# untitled2.net
KiCad netlist of a schematic drawn in EAGLE
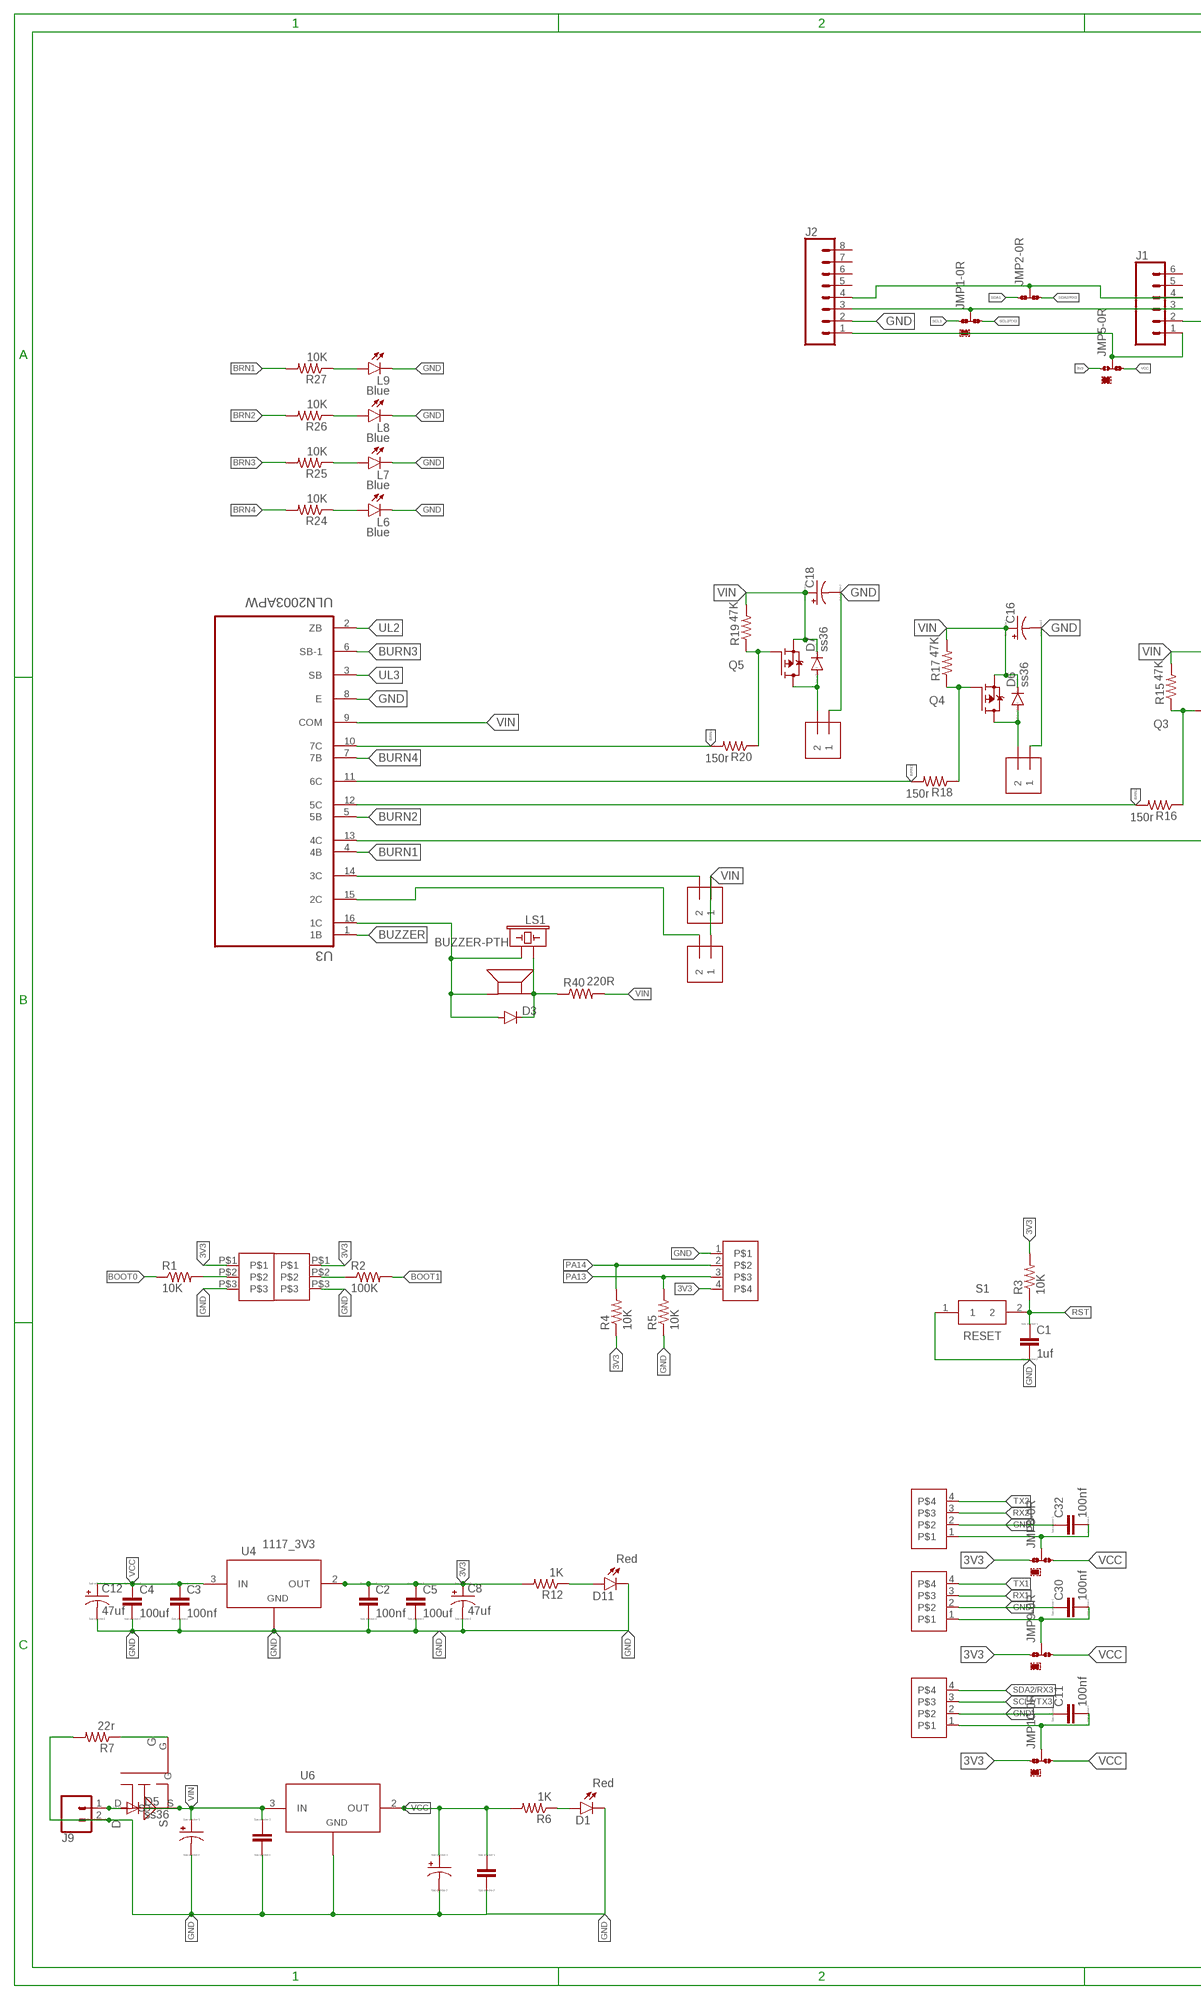
[diagram p0: schematic, sheet 1, part 1 of 2]
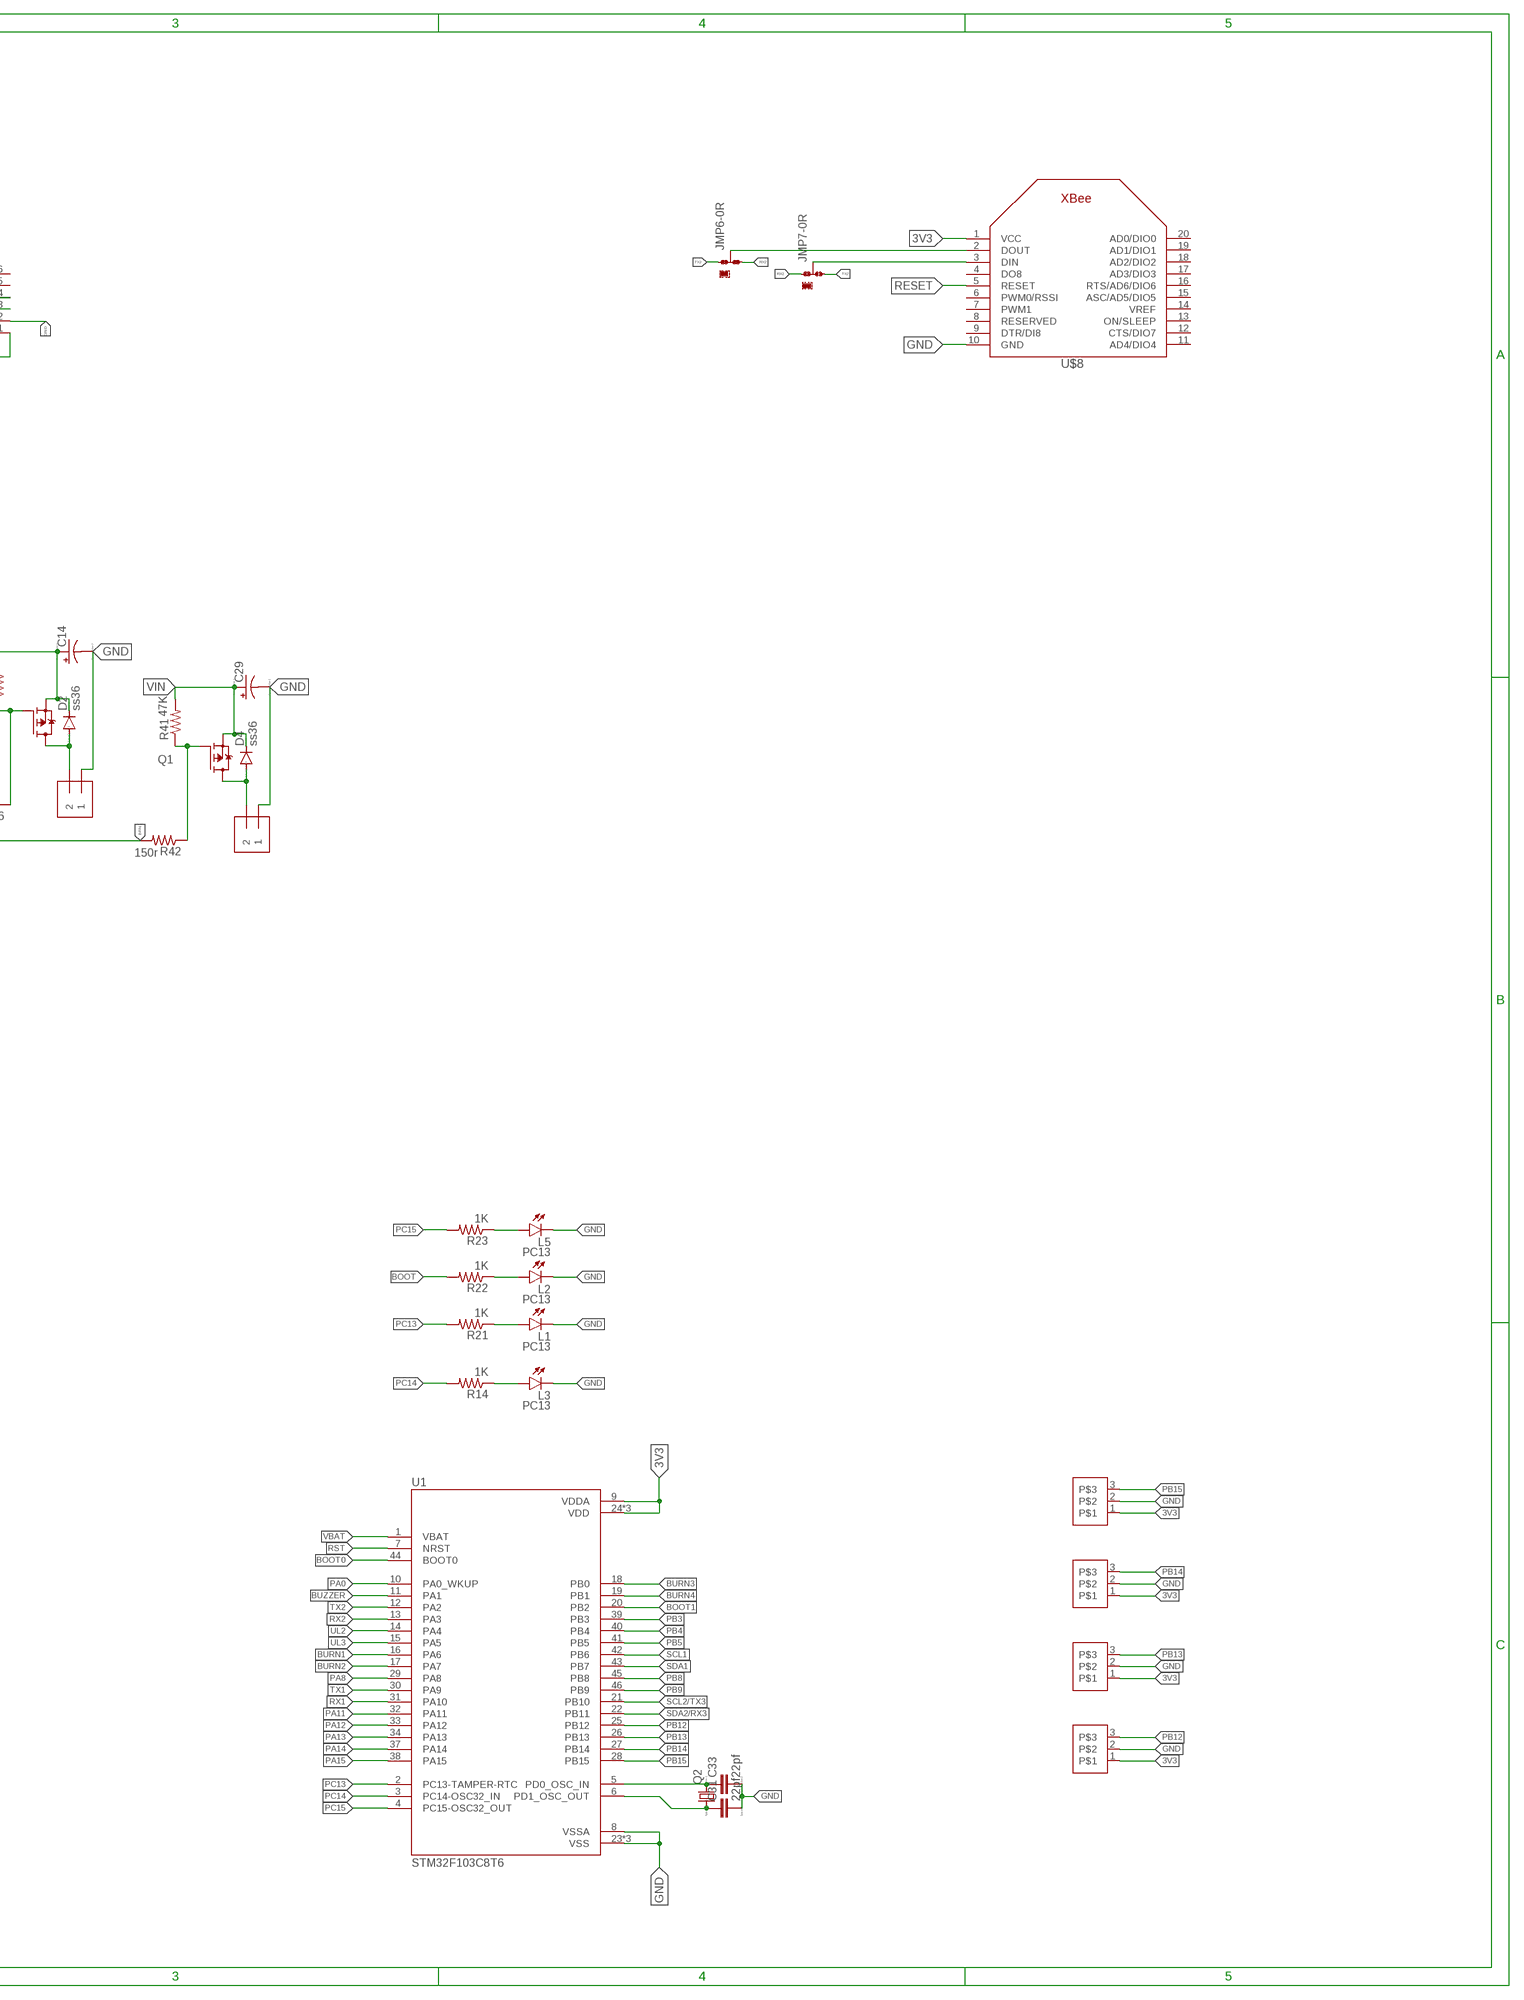
[diagram p1: schematic, sheet 1, part 2 of 2]

(export (version "E")
  (design (tool "Eeschema 10.0.6"))
  (components
    (comp (ref "C1")
      (value "1uf")
      (footprint "eagle-import:C0603")
      (libsource (lib "eagle-import") (part "CAPACITOR_CER4"))
    )
    (comp (ref "C2")
      (value "100nf")
      (footprint "eagle-import:C0603")
      (libsource (lib "eagle-import") (part "CAPACITOR_CER4"))
    )
    (comp (ref "C3")
      (value "100nf")
      (footprint "eagle-import:C0603")
      (libsource (lib "eagle-import") (part "CAPACITOR_CER4"))
    )
    (comp (ref "C4")
      (value "100uf")
      (footprint "eagle-import:C1210")
      (libsource (lib "eagle-import") (part "CAPACITOR_CER9"))
    )
    (comp (ref "C5")
      (value "100uf")
      (footprint "eagle-import:C1210")
      (libsource (lib "eagle-import") (part "CAPACITOR_CER9"))
    )
    (comp (ref "C6")
      (value "100nf")
      (footprint "eagle-import:C0603")
      (libsource (lib "eagle-import") (part "CAPACITOR_CER4"))
    )
    (comp (ref "C7")
      (value "100uf")
      (footprint "eagle-import:PANASONIC_D")
      (libsource (lib "eagle-import") (part "CAPACITOR_POLD"))
    )
    (comp (ref "C8")
      (value "47uf")
      (footprint "eagle-import:PANASONIC_C")
      (libsource (lib "eagle-import") (part "CAPACITOR_POLC"))
    )
    (comp (ref "C9")
      (value "100nf")
      (footprint "eagle-import:C0603")
      (libsource (lib "eagle-import") (part "CAPACITOR_CER4"))
    )
    (comp (ref "C10")
      (value "100uf")
      (footprint "eagle-import:PANASONIC_D")
      (libsource (lib "eagle-import") (part "CAPACITOR_POLD"))
    )
    (comp (ref "C11")
      (value "100nf")
      (footprint "eagle-import:C0603")
      (libsource (lib "eagle-import") (part "CAPACITOR_CER4"))
    )
    (comp (ref "C12")
      (value "47uf")
      (footprint "eagle-import:PANASONIC_C")
      (libsource (lib "eagle-import") (part "CAPACITOR_POLC"))
    )
    (comp (ref "C14")
      (value "CAPACITOR_POLC")
      (footprint "eagle-import:PANASONIC_C")
      (libsource (lib "eagle-import") (part "CAPACITOR_POLC"))
    )
    (comp (ref "C16")
      (value "CAPACITOR_POLC")
      (footprint "eagle-import:PANASONIC_C")
      (libsource (lib "eagle-import") (part "CAPACITOR_POLC"))
    )
    (comp (ref "C18")
      (value "CAPACITOR_POLC")
      (footprint "eagle-import:PANASONIC_C")
      (libsource (lib "eagle-import") (part "CAPACITOR_POLC"))
    )
    (comp (ref "C29")
      (value "CAPACITOR_POLC")
      (footprint "eagle-import:PANASONIC_C")
      (libsource (lib "eagle-import") (part "CAPACITOR_POLC"))
    )
    (comp (ref "C30")
      (value "100nf")
      (footprint "eagle-import:C0603")
      (libsource (lib "eagle-import") (part "CAPACITOR_CER4"))
    )
    (comp (ref "C31")
      (value "22pf")
      (footprint "eagle-import:C0603")
      (libsource (lib "eagle-import") (part "CAPACITOR_CER4"))
    )
    (comp (ref "C32")
      (value "100nf")
      (footprint "eagle-import:C0603")
      (libsource (lib "eagle-import") (part "CAPACITOR_CER4"))
    )
    (comp (ref "C33")
      (value "22pf")
      (footprint "eagle-import:C0603")
      (libsource (lib "eagle-import") (part "CAPACITOR_CER4"))
    )
    (comp (ref "D1")
      (value "Red")
      (footprint "eagle-import:0603_LED_GREEN")
      (libsource (lib "eagle-import") (part "LED0603_R"))
    )
    (comp (ref "D2")
      (value "ss36")
      (footprint "eagle-import:DO-214AC")
      (libsource (lib "eagle-import") (part "DIODEAC2"))
    )
    (comp (ref "D3")
      (value "DIODESOD")
      (footprint "eagle-import:SOD-323")
      (libsource (lib "eagle-import") (part "DIODESOD"))
    )
    (comp (ref "D4")
      (value "ss36")
      (footprint "eagle-import:DO-214AC")
      (libsource (lib "eagle-import") (part "DIODEAC2"))
    )
    (comp (ref "D5")
      (value "ss36")
      (footprint "eagle-import:DO-214AC")
      (libsource (lib "eagle-import") (part "DIODEAC2"))
    )
    (comp (ref "D6")
      (value "ss36")
      (footprint "eagle-import:DO-214AC")
      (libsource (lib "eagle-import") (part "DIODEAC2"))
    )
    (comp (ref "D7")
      (value "ss36")
      (footprint "eagle-import:DO-214AC")
      (libsource (lib "eagle-import") (part "DIODEAC2"))
    )
    (comp (ref "D11")
      (value "Red")
      (footprint "eagle-import:0603_LED_GREEN")
      (libsource (lib "eagle-import") (part "LED0603_R"))
    )
    (comp (ref "J1")
      (value "CONN_06NO_SILK_NO_POP")
      (footprint "eagle-import:1X06_NO_SILK")
      (libsource (lib "eagle-import") (part "CONN_06NO_SILK_NO_POP"))
    )
    (comp (ref "J2")
      (value "CONN_08NO_SILK_FEMALE_PTH")
      (footprint "eagle-import:1X08_NO_SILK")
      (libsource (lib "eagle-import") (part "CONN_08NO_SILK_FEMALE_PTH"))
    )
    (comp (ref "J9")
      (value "CONN_025MM")
      (footprint "eagle-import:SCREWTERMINAL-5MM-2")
      (libsource (lib "eagle-import") (part "CONN_025MM"))
    )
    (comp (ref "JMP1")
      (value "0R-JUMPA")
      (footprint "eagle-import:A0R-JMP")
      (libsource (lib "eagle-import") (part "0R-JUMPA"))
    )
    (comp (ref "JMP2")
      (value "0R-JUMPA")
      (footprint "eagle-import:A0R-JMP")
      (libsource (lib "eagle-import") (part "0R-JUMPA"))
    )
    (comp (ref "JMP5")
      (value "0R-JUMPA")
      (footprint "eagle-import:A0R-JMP")
      (libsource (lib "eagle-import") (part "0R-JUMPA"))
    )
    (comp (ref "JMP6")
      (value "0R-JUMPA")
      (footprint "eagle-import:A0R-JMP")
      (libsource (lib "eagle-import") (part "0R-JUMPA"))
    )
    (comp (ref "JMP7")
      (value "0R-JUMPA")
      (footprint "eagle-import:A0R-JMP")
      (libsource (lib "eagle-import") (part "0R-JUMPA"))
    )
    (comp (ref "JMP8")
      (value "0R-JUMPA")
      (footprint "eagle-import:A0R-JMP")
      (libsource (lib "eagle-import") (part "0R-JUMPA"))
    )
    (comp (ref "JMP9")
      (value "0R-JUMPA")
      (footprint "eagle-import:A0R-JMP")
      (libsource (lib "eagle-import") (part "0R-JUMPA"))
    )
    (comp (ref "JMP10")
      (value "0R-JUMPA")
      (footprint "eagle-import:A0R-JMP")
      (libsource (lib "eagle-import") (part "0R-JUMPA"))
    )
    (comp (ref "L1")
      (value "PC13")
      (footprint "eagle-import:0603_LED_GREEN")
      (libsource (lib "eagle-import") (part "LED0603_R"))
    )
    (comp (ref "L2")
      (value "PC13")
      (footprint "eagle-import:0603_LED_GREEN")
      (libsource (lib "eagle-import") (part "LED0603_R"))
    )
    (comp (ref "L3")
      (value "PC13")
      (footprint "eagle-import:0603_LED_GREEN")
      (libsource (lib "eagle-import") (part "LED0603_R"))
    )
    (comp (ref "L5")
      (value "PC13")
      (footprint "eagle-import:0603_LED_GREEN")
      (libsource (lib "eagle-import") (part "LED0603_R"))
    )
    (comp (ref "L6")
      (value "Blue")
      (footprint "eagle-import:0603_LED_GREEN")
      (libsource (lib "eagle-import") (part "LED0603_R"))
    )
    (comp (ref "L7")
      (value "Blue")
      (footprint "eagle-import:0603_LED_GREEN")
      (libsource (lib "eagle-import") (part "LED0603_R"))
    )
    (comp (ref "L8")
      (value "Blue")
      (footprint "eagle-import:0603_LED_GREEN")
      (libsource (lib "eagle-import") (part "LED0603_R"))
    )
    (comp (ref "L9")
      (value "Blue")
      (footprint "eagle-import:0603_LED_GREEN")
      (libsource (lib "eagle-import") (part "LED0603_R"))
    )
    (comp (ref "LS1")
      (value "BUZZER-PTH")
      (footprint "eagle-import:BUZZER-12MM")
      (libsource (lib "eagle-import") (part "BUZZER-PTH"))
    )
    (comp (ref "Q1")
      (value "FDD4141TO252")
      (footprint "eagle-import:TO252")
      (libsource (lib "eagle-import") (part "FDD4141TO252"))
    )
    (comp (ref "Q2")
      (value "CRYSTALHC49U-V")
      (footprint "eagle-import:HC49U-V")
      (libsource (lib "eagle-import") (part "CRYSTALHC49U-V"))
    )
    (comp (ref "Q3")
      (value "FDD4141TO252")
      (footprint "eagle-import:TO252")
      (libsource (lib "eagle-import") (part "FDD4141TO252"))
    )
    (comp (ref "Q4")
      (value "FDD4141TO252")
      (footprint "eagle-import:TO252")
      (libsource (lib "eagle-import") (part "FDD4141TO252"))
    )
    (comp (ref "Q5")
      (value "FDD4141TO252")
      (footprint "eagle-import:TO252")
      (libsource (lib "eagle-import") (part "FDD4141TO252"))
    )
    (comp (ref "Q6")
      (value "AON7401")
      (footprint "eagle-import:DFN-8_3X3")
      (libsource (lib "eagle-import") (part "AON7401"))
    )
    (comp (ref "R1")
      (value "10K")
      (footprint "eagle-import:R0603")
      (libsource (lib "eagle-import") (part "RESISTOR0603"))
    )
    (comp (ref "R2")
      (value "100K")
      (footprint "eagle-import:R0603")
      (libsource (lib "eagle-import") (part "RESISTOR0603"))
    )
    (comp (ref "R3")
      (value "10K")
      (footprint "eagle-import:R0603")
      (libsource (lib "eagle-import") (part "RESISTOR0603"))
    )
    (comp (ref "R4")
      (value "10K")
      (footprint "eagle-import:R0603")
      (libsource (lib "eagle-import") (part "RESISTOR0603"))
    )
    (comp (ref "R5")
      (value "10K")
      (footprint "eagle-import:R0603")
      (libsource (lib "eagle-import") (part "RESISTOR0603"))
    )
    (comp (ref "R6")
      (value "1K")
      (footprint "eagle-import:R0603")
      (libsource (lib "eagle-import") (part "RESISTOR0603"))
    )
    (comp (ref "R7")
      (value "22r")
      (footprint "eagle-import:R0603")
      (libsource (lib "eagle-import") (part "RESISTOR0603"))
    )
    (comp (ref "R12")
      (value "1K")
      (footprint "eagle-import:R0603")
      (libsource (lib "eagle-import") (part "RESISTOR0603"))
    )
    (comp (ref "R14")
      (value "1K")
      (footprint "eagle-import:R0603")
      (libsource (lib "eagle-import") (part "RESISTOR0603"))
    )
    (comp (ref "R15")
      (value "47K")
      (footprint "eagle-import:R0603")
      (libsource (lib "eagle-import") (part "RESISTOR0603"))
    )
    (comp (ref "R16")
      (value "150r")
      (footprint "eagle-import:R0603")
      (libsource (lib "eagle-import") (part "RESISTOR0603"))
    )
    (comp (ref "R17")
      (value "47K")
      (footprint "eagle-import:R0603")
      (libsource (lib "eagle-import") (part "RESISTOR0603"))
    )
    (comp (ref "R18")
      (value "150r")
      (footprint "eagle-import:R0603")
      (libsource (lib "eagle-import") (part "RESISTOR0603"))
    )
    (comp (ref "R19")
      (value "47K")
      (footprint "eagle-import:R0603")
      (libsource (lib "eagle-import") (part "RESISTOR0603"))
    )
    (comp (ref "R20")
      (value "150r")
      (footprint "eagle-import:R0603")
      (libsource (lib "eagle-import") (part "RESISTOR0603"))
    )
    (comp (ref "R21")
      (value "1K")
      (footprint "eagle-import:R0603")
      (libsource (lib "eagle-import") (part "RESISTOR0603"))
    )
    (comp (ref "R22")
      (value "1K")
      (footprint "eagle-import:R0603")
      (libsource (lib "eagle-import") (part "RESISTOR0603"))
    )
    (comp (ref "R23")
      (value "1K")
      (footprint "eagle-import:R0603")
      (libsource (lib "eagle-import") (part "RESISTOR0603"))
    )
    (comp (ref "R24")
      (value "10K")
      (footprint "eagle-import:R0603")
      (libsource (lib "eagle-import") (part "RESISTOR0603"))
    )
    (comp (ref "R25")
      (value "10K")
      (footprint "eagle-import:R0603")
      (libsource (lib "eagle-import") (part "RESISTOR0603"))
    )
    (comp (ref "R26")
      (value "10K")
      (footprint "eagle-import:R0603")
      (libsource (lib "eagle-import") (part "RESISTOR0603"))
    )
    (comp (ref "R27")
      (value "10K")
      (footprint "eagle-import:R0603")
      (libsource (lib "eagle-import") (part "RESISTOR0603"))
    )
    (comp (ref "R40")
      (value "220R")
      (footprint "eagle-import:R0603")
      (libsource (lib "eagle-import") (part "RESISTOR0603"))
    )
    (comp (ref "R41")
      (value "47K")
      (footprint "eagle-import:R0603")
      (libsource (lib "eagle-import") (part "RESISTOR0603"))
    )
    (comp (ref "R42")
      (value "150r")
      (footprint "eagle-import:R0603")
      (libsource (lib "eagle-import") (part "RESISTOR0603"))
    )
    (comp (ref "S1")
      (value "RESET")
      (footprint "eagle-import:SKRK")
      (fields (field (name "MF") "ALPS") (field (name "MP") "SKRKAEE010"))
      (libsource (lib "eagle-import") (part "SKRKAEE010"))
    )
    (comp (ref "U$1")
      (value "FML_1X32MM")
      (footprint "eagle-import:1X3_2MM")
      (libsource (lib "eagle-import") (part "FML_1X32MM"))
    )
    (comp (ref "U$2")
      (value "FML_1X32MM")
      (footprint "eagle-import:1X3_2MM")
      (libsource (lib "eagle-import") (part "FML_1X32MM"))
    )
    (comp (ref "U$3")
      (value "FML_1X4")
      (footprint "eagle-import:HDRVR4W64P254_1X4_1016X240X800B")
      (libsource (lib "eagle-import") (part "FML_1X4"))
    )
    (comp (ref "U$4")
      (value "1X2")
      (footprint "eagle-import:1X2")
      (libsource (lib "eagle-import") (part "1X2"))
    )
    (comp (ref "U$5")
      (value "1X2")
      (footprint "eagle-import:1X2")
      (libsource (lib "eagle-import") (part "1X2"))
    )
    (comp (ref "U$6")
      (value "1X2")
      (footprint "eagle-import:1X2")
      (libsource (lib "eagle-import") (part "1X2"))
    )
    (comp (ref "U$7")
      (value "FML_1X4")
      (footprint "eagle-import:HDRVR4W64P254_1X4_1016X240X800B")
      (libsource (lib "eagle-import") (part "FML_1X4"))
    )
    (comp (ref "U$8")
      (value "XBEE")
      (footprint "eagle-import:XBEE")
      (libsource (lib "eagle-import") (part "XBEE"))
    )
    (comp (ref "U$9")
      (value "Z_STOP")
      (footprint "eagle-import:HDRVR3W64P254_1X3_762X240X800B")
      (libsource (lib "eagle-import") (part "FML_1X3"))
    )
    (comp (ref "U$11")
      (value "FML_1X4")
      (footprint "eagle-import:HDRVR4W64P254_1X4_1016X240X800B")
      (libsource (lib "eagle-import") (part "FML_1X4"))
    )
    (comp (ref "U$12")
      (value "FML_1X4")
      (footprint "eagle-import:HDRVR4W64P254_1X4_1016X240X800B")
      (libsource (lib "eagle-import") (part "FML_1X4"))
    )
    (comp (ref "U$13")
      (value "Z_STOP")
      (footprint "eagle-import:HDRVR3W64P254_1X3_762X240X800B")
      (libsource (lib "eagle-import") (part "FML_1X3"))
    )
    (comp (ref "U$14")
      (value "Y_STOP")
      (footprint "eagle-import:HDRVR3W64P254_1X3_762X240X800B")
      (libsource (lib "eagle-import") (part "FML_1X3"))
    )
    (comp (ref "U$15")
      (value "X_STOP")
      (footprint "eagle-import:HDRVR3W64P254_1X3_762X240X800B")
      (libsource (lib "eagle-import") (part "FML_1X3"))
    )
    (comp (ref "U$19")
      (value "7.5X7.5_BUZZER")
      (footprint "eagle-import:SMD_7.5_BUZZER")
      (libsource (lib "eagle-import") (part "7.5X7.5_BUZZER"))
    )
    (comp (ref "U$20")
      (value "1X2")
      (footprint "eagle-import:1X2")
      (libsource (lib "eagle-import") (part "1X2"))
    )
    (comp (ref "U$21")
      (value "1X2")
      (footprint "eagle-import:1X2")
      (libsource (lib "eagle-import") (part "1X2"))
    )
    (comp (ref "U$22")
      (value "1X2")
      (footprint "eagle-import:1X2")
      (libsource (lib "eagle-import") (part "1X2"))
    )
    (comp (ref "U1")
      (value "STM32F103C8T6")
      (footprint "eagle-import:QFP50P900X900X160-48N")
      (fields (field (name "MF") "STMicroelectronics"))
      (libsource (lib "eagle-import") (part "STM32F103C8T6"))
    )
    (comp (ref "U3")
      (value "ULN2003APW")
      (footprint "eagle-import:SOP65P640X120-16N")
      (fields (field (name "MF") "Texas Instruments"))
      (libsource (lib "eagle-import") (part "ULN2003APW"))
    )
    (comp (ref "U4")
      (value "1117_3V3")
      (footprint "eagle-import:SOT-223")
      (fields
        (field (name "DIGIKEY_PART_NUMBER") "NCP1117ST33T3GOSTR-ND")
        (field (name "MANUFACTURER") "ON Semiconductor")
        (field (name "MPN") "NCP1117ST33T3G")
        (field (name "CREATED_BY") "PCBLayout.com")
      )
      (libsource (lib "eagle-import") (part "NCP1117ST33T3G"))
    )
    (comp (ref "U6")
      (value "1117_3V3")
      (footprint "eagle-import:SOT-223")
      (fields
        (field (name "DIGIKEY_PART_NUMBER") "NCP1117ST33T3GOSTR-ND")
        (field (name "MANUFACTURER") "ON Semiconductor")
        (field (name "MPN") "NCP1117ST33T3G")
        (field (name "CREATED_BY") "PCBLayout.com")
      )
      (libsource (lib "eagle-import") (part "NCP1117ST33T3G"))
    )
  )
  (nets
    (net (code "1") (name "3V3") (class "Default")
      (node (ref "C2") (pin "1") (pinfunction "1_1") (pintype "passive"))
      (node (ref "C5") (pin "1") (pinfunction "1_1") (pintype "passive"))
      (node (ref "C8") (pin "+") (pinfunction "+_+") (pintype "passive"))
      (node (ref "JMP10") (pin "1") (pinfunction "1_1") (pintype "passive"))
      (node (ref "JMP5") (pin "1") (pinfunction "1_1") (pintype "passive"))
      (node (ref "JMP8") (pin "1") (pinfunction "1_1") (pintype "passive"))
      (node (ref "JMP9") (pin "1") (pinfunction "1_1") (pintype "passive"))
      (node (ref "R12") (pin "2") (pinfunction "2_2") (pintype "passive"))
      (node (ref "R3") (pin "2") (pinfunction "2_2") (pintype "passive"))
      (node (ref "R4") (pin "1") (pinfunction "1_1") (pintype "passive"))
      (node (ref "U$1") (pin "P$1") (pinfunction "P$1_P$1") (pintype "bidirectional"))
      (node (ref "U$13") (pin "1") (pinfunction "P$1_1") (pintype "bidirectional"))
      (node (ref "U$14") (pin "1") (pinfunction "P$1_1") (pintype "bidirectional"))
      (node (ref "U$15") (pin "1") (pinfunction "P$1_1") (pintype "bidirectional"))
      (node (ref "U$2") (pin "P$1") (pinfunction "P$1_P$1") (pintype "bidirectional"))
      (node (ref "U$3") (pin "4") (pinfunction "P$4_4") (pintype "bidirectional"))
      (node (ref "U$8") (pin "1") (pinfunction "VCC_1") (pintype "power_in"))
      (node (ref "U$9") (pin "1") (pinfunction "P$1_1") (pintype "bidirectional"))
      (node (ref "U1") (pin "24") (pinfunction "VDD_24") (pintype "power_in"))
      (node (ref "U1") (pin "36") (pinfunction "VDD_36") (pintype "power_in"))
      (node (ref "U1") (pin "48") (pinfunction "VDD_48") (pintype "power_in"))
      (node (ref "U1") (pin "9") (pinfunction "VDDA_9") (pintype "power_in"))
      (node (ref "U4") (pin "2") (pinfunction "OUT_2") (pintype "output"))
      (node (ref "U4") (pin "4") (pinfunction "4_4") (pintype "passive"))
    )
    (net (code "2") (name "BOOT") (class "Default")
      (node (ref "R1") (pin "2") (pinfunction "2_2") (pintype "passive"))
      (node (ref "R22") (pin "2") (pinfunction "2_2") (pintype "passive"))
      (node (ref "U$2") (pin "P$2") (pinfunction "P$2_P$2") (pintype "bidirectional"))
    )
    (net (code "3") (name "BOOT0") (class "Default")
      (node (ref "R1") (pin "1") (pinfunction "1_1") (pintype "passive"))
      (node (ref "U1") (pin "44") (pinfunction "BOOT0_44") (pintype "input"))
    )
    (net (code "4") (name "BOOT1") (class "Default")
      (node (ref "R2") (pin "2") (pinfunction "2_2") (pintype "passive"))
      (node (ref "U1") (pin "20") (pinfunction "PB2_20") (pintype "bidirectional"))
    )
    (net (code "5") (name "BRN1") (class "Default")
      (node (ref "R27") (pin "2") (pinfunction "2_2") (pintype "passive"))
      (node (ref "R42") (pin "2") (pinfunction "2_2") (pintype "passive"))
      (node (ref "U3") (pin "13") (pinfunction "4C_13") (pintype "bidirectional"))
    )
    (net (code "6") (name "BRN2") (class "Default")
      (node (ref "R16") (pin "2") (pinfunction "2_2") (pintype "passive"))
      (node (ref "R26") (pin "2") (pinfunction "2_2") (pintype "passive"))
      (node (ref "U3") (pin "12") (pinfunction "5C_12") (pintype "bidirectional"))
    )
    (net (code "7") (name "BRN3") (class "Default")
      (node (ref "R18") (pin "2") (pinfunction "2_2") (pintype "passive"))
      (node (ref "R25") (pin "2") (pinfunction "2_2") (pintype "passive"))
      (node (ref "U3") (pin "11") (pinfunction "6C_11") (pintype "bidirectional"))
    )
    (net (code "8") (name "BRN4") (class "Default")
      (node (ref "R20") (pin "2") (pinfunction "2_2") (pintype "passive"))
      (node (ref "R24") (pin "2") (pinfunction "2_2") (pintype "passive"))
      (node (ref "U3") (pin "10") (pinfunction "7C_10") (pintype "bidirectional"))
    )
    (net (code "9") (name "BURN1") (class "Default")
      (node (ref "U1") (pin "16") (pinfunction "PA6_16") (pintype "bidirectional"))
      (node (ref "U3") (pin "4") (pinfunction "4B_4") (pintype "bidirectional"))
    )
    (net (code "10") (name "BURN2") (class "Default")
      (node (ref "U1") (pin "17") (pinfunction "PA7_17") (pintype "bidirectional"))
      (node (ref "U3") (pin "5") (pinfunction "5B_5") (pintype "bidirectional"))
    )
    (net (code "11") (name "BURN3") (class "Default")
      (node (ref "U1") (pin "18") (pinfunction "PB0_18") (pintype "bidirectional"))
      (node (ref "U3") (pin "6") (pinfunction "SB-1_6") (pintype "bidirectional"))
    )
    (net (code "12") (name "BURN4") (class "Default")
      (node (ref "U1") (pin "19") (pinfunction "PB1_19") (pintype "bidirectional"))
      (node (ref "U3") (pin "7") (pinfunction "7B_7") (pintype "bidirectional"))
    )
    (net (code "13") (name "BUZZER") (class "Default")
      (node (ref "U1") (pin "11") (pinfunction "PA1_11") (pintype "bidirectional"))
      (node (ref "U3") (pin "1") (pinfunction "1B_1") (pintype "bidirectional"))
    )
    (net (code "14") (name "GND") (class "Default")
      (node (ref "C1") (pin "2") (pinfunction "2_2") (pintype "passive"))
      (node (ref "C10") (pin "-") (pinfunction "-_-") (pintype "passive"))
      (node (ref "C11") (pin "1") (pinfunction "1_1") (pintype "passive"))
      (node (ref "C12") (pin "-") (pinfunction "-_-") (pintype "passive"))
      (node (ref "C14") (pin "-") (pinfunction "-_-") (pintype "passive"))
      (node (ref "C16") (pin "-") (pinfunction "-_-") (pintype "passive"))
      (node (ref "C18") (pin "-") (pinfunction "-_-") (pintype "passive"))
      (node (ref "C2") (pin "2") (pinfunction "2_2") (pintype "passive"))
      (node (ref "C29") (pin "-") (pinfunction "-_-") (pintype "passive"))
      (node (ref "C3") (pin "2") (pinfunction "2_2") (pintype "passive"))
      (node (ref "C30") (pin "1") (pinfunction "1_1") (pintype "passive"))
      (node (ref "C31") (pin "2") (pinfunction "2_2") (pintype "passive"))
      (node (ref "C32") (pin "1") (pinfunction "1_1") (pintype "passive"))
      (node (ref "C33") (pin "2") (pinfunction "2_2") (pintype "passive"))
      (node (ref "C4") (pin "2") (pinfunction "2_2") (pintype "passive"))
      (node (ref "C5") (pin "2") (pinfunction "2_2") (pintype "passive"))
      (node (ref "C6") (pin "2") (pinfunction "2_2") (pintype "passive"))
      (node (ref "C7") (pin "-") (pinfunction "-_-") (pintype "passive"))
      (node (ref "C8") (pin "-") (pinfunction "-_-") (pintype "passive"))
      (node (ref "C9") (pin "2") (pinfunction "2_2") (pintype "passive"))
      (node (ref "D1") (pin "C") (pinfunction "C_C") (pintype "passive"))
      (node (ref "D11") (pin "C") (pinfunction "C_C") (pintype "passive"))
      (node (ref "J1") (pin "2") (pinfunction "2_2") (pintype "passive"))
      (node (ref "J2") (pin "2") (pinfunction "2_2") (pintype "passive"))
      (node (ref "J9") (pin "2") (pinfunction "2_2") (pintype "passive"))
      (node (ref "L1") (pin "C") (pinfunction "C_C") (pintype "passive"))
      (node (ref "L2") (pin "C") (pinfunction "C_C") (pintype "passive"))
      (node (ref "L3") (pin "C") (pinfunction "C_C") (pintype "passive"))
      (node (ref "L5") (pin "C") (pinfunction "C_C") (pintype "passive"))
      (node (ref "L6") (pin "C") (pinfunction "C_C") (pintype "passive"))
      (node (ref "L7") (pin "C") (pinfunction "C_C") (pintype "passive"))
      (node (ref "L8") (pin "C") (pinfunction "C_C") (pintype "passive"))
      (node (ref "L9") (pin "C") (pinfunction "C_C") (pintype "passive"))
      (node (ref "R5") (pin "1") (pinfunction "1_1") (pintype "passive"))
      (node (ref "R7") (pin "2") (pinfunction "2_2") (pintype "passive"))
      (node (ref "S1") (pin "1") (pinfunction "1_1") (pintype "passive"))
      (node (ref "U$1") (pin "P$3") (pinfunction "P$3_P$3") (pintype "bidirectional"))
      (node (ref "U$11") (pin "2") (pinfunction "P$2_2") (pintype "bidirectional"))
      (node (ref "U$12") (pin "2") (pinfunction "P$2_2") (pintype "bidirectional"))
      (node (ref "U$13") (pin "2") (pinfunction "P$2_2") (pintype "bidirectional"))
      (node (ref "U$14") (pin "2") (pinfunction "P$2_2") (pintype "bidirectional"))
      (node (ref "U$15") (pin "2") (pinfunction "P$2_2") (pintype "bidirectional"))
      (node (ref "U$2") (pin "P$3") (pinfunction "P$3_P$3") (pintype "bidirectional"))
      (node (ref "U$21") (pin "P$1") (pinfunction "1_P$1") (pintype "passive"))
      (node (ref "U$3") (pin "1") (pinfunction "P$1_1") (pintype "bidirectional"))
      (node (ref "U$4") (pin "P$1") (pinfunction "1_P$1") (pintype "passive"))
      (node (ref "U$5") (pin "P$1") (pinfunction "1_P$1") (pintype "passive"))
      (node (ref "U$6") (pin "P$1") (pinfunction "1_P$1") (pintype "passive"))
      (node (ref "U$7") (pin "2") (pinfunction "P$2_2") (pintype "bidirectional"))
      (node (ref "U$8") (pin "10") (pinfunction "GND_10") (pintype "power_in"))
      (node (ref "U$9") (pin "2") (pinfunction "P$2_2") (pintype "bidirectional"))
      (node (ref "U1") (pin "23") (pinfunction "VSS_23") (pintype "power_in"))
      (node (ref "U1") (pin "35") (pinfunction "VSS_35") (pintype "power_in"))
      (node (ref "U1") (pin "47") (pinfunction "VSS_47") (pintype "power_in"))
      (node (ref "U1") (pin "8") (pinfunction "VSSA_8") (pintype "power_in"))
      (node (ref "U3") (pin "8") (pinfunction "E_8") (pintype "bidirectional"))
      (node (ref "U4") (pin "1") (pinfunction "ADJ/GND_1") (pintype "power_in"))
      (node (ref "U6") (pin "1") (pinfunction "ADJ/GND_1") (pintype "power_in"))
    )
    (net (code "15") (name "Net-(D1-PadA)") (class "Default")
      (node (ref "D1") (pin "A") (pinfunction "A_A") (pintype "passive"))
      (node (ref "R6") (pin "1") (pinfunction "1_1") (pintype "passive"))
    )
    (net (code "16") (name "Net-(D5-PadA)") (class "Default")
      (node (ref "D5") (pin "A") (pinfunction "A_A") (pintype "passive"))
      (node (ref "J9") (pin "1") (pinfunction "1_1") (pintype "passive"))
      (node (ref "Q6") (pin "D") (pinfunction "D_D") (pintype "bidirectional"))
    )
    (net (code "17") (name "Net-(D11-PadA)") (class "Default")
      (node (ref "D11") (pin "A") (pinfunction "A_A") (pintype "passive"))
      (node (ref "R12") (pin "1") (pinfunction "1_1") (pintype "passive"))
    )
    (net (code "18") (name "Net-(J1-Pad1)") (class "Default")
      (node (ref "J1") (pin "1") (pinfunction "1_1") (pintype "passive"))
      (node (ref "J2") (pin "1") (pinfunction "1_1") (pintype "passive"))
      (node (ref "JMP5") (pin "2") (pinfunction "2_2") (pintype "passive"))
    )
    (net (code "19") (name "Net-(J1-Pad3)") (class "Default")
      (node (ref "J1") (pin "3") (pinfunction "3_3") (pintype "passive"))
      (node (ref "J2") (pin "3") (pinfunction "3_3") (pintype "passive"))
      (node (ref "JMP1") (pin "2") (pinfunction "2_2") (pintype "passive"))
    )
    (net (code "20") (name "Net-(J1-Pad4)") (class "Default")
      (node (ref "J1") (pin "4") (pinfunction "4_4") (pintype "passive"))
      (node (ref "J2") (pin "4") (pinfunction "4_4") (pintype "passive"))
      (node (ref "JMP2") (pin "2") (pinfunction "2_2") (pintype "passive"))
    )
    (net (code "21") (name "Net-(L1-PadA)") (class "Default")
      (node (ref "L1") (pin "A") (pinfunction "A_A") (pintype "passive"))
      (node (ref "R21") (pin "1") (pinfunction "1_1") (pintype "passive"))
    )
    (net (code "22") (name "Net-(L2-PadA)") (class "Default")
      (node (ref "L2") (pin "A") (pinfunction "A_A") (pintype "passive"))
      (node (ref "R22") (pin "1") (pinfunction "1_1") (pintype "passive"))
    )
    (net (code "23") (name "Net-(L3-PadA)") (class "Default")
      (node (ref "L3") (pin "A") (pinfunction "A_A") (pintype "passive"))
      (node (ref "R14") (pin "1") (pinfunction "1_1") (pintype "passive"))
    )
    (net (code "24") (name "Net-(L5-PadA)") (class "Default")
      (node (ref "L5") (pin "A") (pinfunction "A_A") (pintype "passive"))
      (node (ref "R23") (pin "1") (pinfunction "1_1") (pintype "passive"))
    )
    (net (code "25") (name "Net-(L6-PadA)") (class "Default")
      (node (ref "L6") (pin "A") (pinfunction "A_A") (pintype "passive"))
      (node (ref "R24") (pin "1") (pinfunction "1_1") (pintype "passive"))
    )
    (net (code "26") (name "Net-(L7-PadA)") (class "Default")
      (node (ref "L7") (pin "A") (pinfunction "A_A") (pintype "passive"))
      (node (ref "R25") (pin "1") (pinfunction "1_1") (pintype "passive"))
    )
    (net (code "27") (name "Net-(L8-PadA)") (class "Default")
      (node (ref "L8") (pin "A") (pinfunction "A_A") (pintype "passive"))
      (node (ref "R26") (pin "1") (pinfunction "1_1") (pintype "passive"))
    )
    (net (code "28") (name "Net-(L9-PadA)") (class "Default")
      (node (ref "L9") (pin "A") (pinfunction "A_A") (pintype "passive"))
      (node (ref "R27") (pin "1") (pinfunction "1_1") (pintype "passive"))
    )
    (net (code "29") (name "Net-(LS1-1)") (class "Default")
      (node (ref "D3") (pin "C") (pinfunction "C_C") (pintype "passive"))
      (node (ref "LS1") (pin "+") (pinfunction "1_+") (pintype "passive"))
      (node (ref "R40") (pin "1") (pinfunction "1_1") (pintype "passive"))
      (node (ref "U$19") (pin "+") (pinfunction "+_+") (pintype "bidirectional"))
    )
    (net (code "30") (name "Net-(LS1-2)") (class "Default")
      (node (ref "D3") (pin "A") (pinfunction "A_A") (pintype "passive"))
      (node (ref "LS1") (pin "-") (pinfunction "2_-") (pintype "passive"))
      (node (ref "U$19") (pin "-") (pinfunction "-_-") (pintype "bidirectional"))
      (node (ref "U3") (pin "16") (pinfunction "1C_16") (pintype "bidirectional"))
    )
    (net (code "31") (name "Net-(Q1-D)") (class "Default")
      (node (ref "D4") (pin "A") (pinfunction "A_A") (pintype "passive"))
      (node (ref "Q1") (pin "3") (pinfunction "D_3") (pintype "passive"))
      (node (ref "U$21") (pin "P$2") (pinfunction "2_P$2") (pintype "passive"))
    )
    (net (code "32") (name "Net-(Q1-G)") (class "Default")
      (node (ref "Q1") (pin "1") (pinfunction "G_1") (pintype "passive"))
      (node (ref "R41") (pin "1") (pinfunction "1_1") (pintype "passive"))
      (node (ref "R42") (pin "1") (pinfunction "1_1") (pintype "passive"))
    )
    (net (code "33") (name "Net-(Q3-D)") (class "Default")
      (node (ref "D2") (pin "A") (pinfunction "A_A") (pintype "passive"))
      (node (ref "Q3") (pin "3") (pinfunction "D_3") (pintype "passive"))
      (node (ref "U$4") (pin "P$2") (pinfunction "2_P$2") (pintype "passive"))
    )
    (net (code "34") (name "Net-(Q3-G)") (class "Default")
      (node (ref "Q3") (pin "1") (pinfunction "G_1") (pintype "passive"))
      (node (ref "R15") (pin "1") (pinfunction "1_1") (pintype "passive"))
      (node (ref "R16") (pin "1") (pinfunction "1_1") (pintype "passive"))
    )
    (net (code "35") (name "Net-(Q4-D)") (class "Default")
      (node (ref "D6") (pin "A") (pinfunction "A_A") (pintype "passive"))
      (node (ref "Q4") (pin "3") (pinfunction "D_3") (pintype "passive"))
      (node (ref "U$5") (pin "P$2") (pinfunction "2_P$2") (pintype "passive"))
    )
    (net (code "36") (name "Net-(Q4-G)") (class "Default")
      (node (ref "Q4") (pin "1") (pinfunction "G_1") (pintype "passive"))
      (node (ref "R17") (pin "1") (pinfunction "1_1") (pintype "passive"))
      (node (ref "R18") (pin "1") (pinfunction "1_1") (pintype "passive"))
    )
    (net (code "37") (name "Net-(Q5-D)") (class "Default")
      (node (ref "D7") (pin "A") (pinfunction "A_A") (pintype "passive"))
      (node (ref "Q5") (pin "3") (pinfunction "D_3") (pintype "passive"))
      (node (ref "U$6") (pin "P$2") (pinfunction "2_P$2") (pintype "passive"))
    )
    (net (code "38") (name "Net-(Q5-G)") (class "Default")
      (node (ref "Q5") (pin "1") (pinfunction "G_1") (pintype "passive"))
      (node (ref "R19") (pin "1") (pinfunction "1_1") (pintype "passive"))
      (node (ref "R20") (pin "1") (pinfunction "1_1") (pintype "passive"))
    )
    (net (code "39") (name "Net-(Q6-PadG)") (class "Default")
      (node (ref "Q6") (pin "G") (pinfunction "G_G") (pintype "bidirectional"))
      (node (ref "R7") (pin "1") (pinfunction "1_1") (pintype "passive"))
    )
    (net (code "40") (name "Net-(R2-Pad1)") (class "Default")
      (node (ref "R2") (pin "1") (pinfunction "1_1") (pintype "passive"))
      (node (ref "U$1") (pin "P$2") (pinfunction "P$2_P$2") (pintype "bidirectional"))
    )
    (net (code "41") (name "Net-(U$7-P$1)") (class "Default")
      (node (ref "C11") (pin "2") (pinfunction "2_2") (pintype "passive"))
      (node (ref "JMP10") (pin "2") (pinfunction "2_2") (pintype "passive"))
      (node (ref "U$7") (pin "1") (pinfunction "P$1_1") (pintype "bidirectional"))
    )
    (net (code "42") (name "Net-(U$8-DIN)") (class "Default")
      (node (ref "JMP7") (pin "2") (pinfunction "2_2") (pintype "passive"))
      (node (ref "U$8") (pin "3") (pinfunction "DIN_3") (pintype "input"))
    )
    (net (code "43") (name "Net-(U$8-DOUT)") (class "Default")
      (node (ref "JMP6") (pin "2") (pinfunction "2_2") (pintype "passive"))
      (node (ref "U$8") (pin "2") (pinfunction "DOUT_2") (pintype "output"))
    )
    (net (code "44") (name "Net-(U$11-P$1)") (class "Default")
      (node (ref "C32") (pin "2") (pinfunction "2_2") (pintype "passive"))
      (node (ref "JMP8") (pin "2") (pinfunction "2_2") (pintype "passive"))
      (node (ref "U$11") (pin "1") (pinfunction "P$1_1") (pintype "bidirectional"))
    )
    (net (code "45") (name "Net-(U$12-P$1)") (class "Default")
      (node (ref "C30") (pin "2") (pinfunction "2_2") (pintype "passive"))
      (node (ref "JMP9") (pin "2") (pinfunction "2_2") (pintype "passive"))
      (node (ref "U$12") (pin "1") (pinfunction "P$1_1") (pintype "bidirectional"))
    )
    (net (code "46") (name "Net-(U$20-2)") (class "Default")
      (node (ref "U$20") (pin "P$2") (pinfunction "2_P$2") (pintype "passive"))
      (node (ref "U3") (pin "15") (pinfunction "2C_15") (pintype "bidirectional"))
    )
    (net (code "47") (name "Net-(U$22-2)") (class "Default")
      (node (ref "U$22") (pin "P$2") (pinfunction "2_P$2") (pintype "passive"))
      (node (ref "U3") (pin "14") (pinfunction "3C_14") (pintype "bidirectional"))
    )
    (net (code "48") (name "Net-(U1-PD0_OSC_IN)") (class "Default")
      (node (ref "C33") (pin "1") (pinfunction "1_1") (pintype "passive"))
      (node (ref "Q2") (pin "2") (pinfunction "2_2") (pintype "passive"))
      (node (ref "U1") (pin "5") (pinfunction "PD0_OSC_IN_5") (pintype "bidirectional"))
    )
    (net (code "49") (name "Net-(U1-PD1_OSC_OUT)") (class "Default")
      (node (ref "C31") (pin "1") (pinfunction "1_1") (pintype "passive"))
      (node (ref "Q2") (pin "1") (pinfunction "1_1") (pintype "passive"))
      (node (ref "U1") (pin "6") (pinfunction "PD1_OSC_OUT_6") (pintype "bidirectional"))
    )
    (net (code "50") (name "PA0") (class "Default")
      (node (ref "U1") (pin "10") (pinfunction "PA0_WKUP_10") (pintype "bidirectional"))
    )
    (net (code "51") (name "PA8") (class "Default")
      (node (ref "U1") (pin "29") (pinfunction "PA8_29") (pintype "bidirectional"))
    )
    (net (code "52") (name "PA11") (class "Default")
      (node (ref "U1") (pin "32") (pinfunction "PA11_32") (pintype "bidirectional"))
    )
    (net (code "53") (name "PA12") (class "Default")
      (node (ref "U1") (pin "33") (pinfunction "PA12_33") (pintype "bidirectional"))
    )
    (net (code "54") (name "PA13") (class "Default")
      (node (ref "R5") (pin "2") (pinfunction "2_2") (pintype "passive"))
      (node (ref "U$3") (pin "3") (pinfunction "P$3_3") (pintype "bidirectional"))
      (node (ref "U1") (pin "34") (pinfunction "PA13_34") (pintype "bidirectional"))
    )
    (net (code "55") (name "PA14") (class "Default")
      (node (ref "R4") (pin "2") (pinfunction "2_2") (pintype "passive"))
      (node (ref "U$3") (pin "2") (pinfunction "P$2_2") (pintype "bidirectional"))
      (node (ref "U1") (pin "37") (pinfunction "PA14_37") (pintype "bidirectional"))
    )
    (net (code "56") (name "PA15") (class "Default")
      (node (ref "U1") (pin "38") (pinfunction "PA15_38") (pintype "bidirectional"))
    )
    (net (code "57") (name "PB3") (class "Default")
      (node (ref "U1") (pin "39") (pinfunction "PB3_39") (pintype "bidirectional"))
    )
    (net (code "58") (name "PB4") (class "Default")
      (node (ref "U1") (pin "40") (pinfunction "PB4_40") (pintype "bidirectional"))
    )
    (net (code "59") (name "PB5") (class "Default")
      (node (ref "U1") (pin "41") (pinfunction "PB5_41") (pintype "bidirectional"))
    )
    (net (code "60") (name "PB8") (class "Default")
      (node (ref "U1") (pin "45") (pinfunction "PB8_45") (pintype "bidirectional"))
    )
    (net (code "61") (name "PB9") (class "Default")
      (node (ref "U1") (pin "46") (pinfunction "PB9_46") (pintype "bidirectional"))
    )
    (net (code "62") (name "PB12") (class "Default")
      (node (ref "U$15") (pin "3") (pinfunction "P$3_3") (pintype "bidirectional"))
      (node (ref "U1") (pin "25") (pinfunction "PB12_25") (pintype "bidirectional"))
    )
    (net (code "63") (name "PB13") (class "Default")
      (node (ref "U$14") (pin "3") (pinfunction "P$3_3") (pintype "bidirectional"))
      (node (ref "U1") (pin "26") (pinfunction "PB13_26") (pintype "bidirectional"))
    )
    (net (code "64") (name "PB14") (class "Default")
      (node (ref "U$13") (pin "3") (pinfunction "P$3_3") (pintype "bidirectional"))
      (node (ref "U1") (pin "27") (pinfunction "PB14_27") (pintype "bidirectional"))
    )
    (net (code "65") (name "PB15") (class "Default")
      (node (ref "U$9") (pin "3") (pinfunction "P$3_3") (pintype "bidirectional"))
      (node (ref "U1") (pin "28") (pinfunction "PB15_28") (pintype "bidirectional"))
    )
    (net (code "66") (name "PC13") (class "Default")
      (node (ref "R21") (pin "2") (pinfunction "2_2") (pintype "passive"))
      (node (ref "U1") (pin "2") (pinfunction "PC13-TAMPER-RTC_2") (pintype "bidirectional"))
    )
    (net (code "67") (name "PC14") (class "Default")
      (node (ref "R14") (pin "2") (pinfunction "2_2") (pintype "passive"))
      (node (ref "U1") (pin "3") (pinfunction "PC14-OSC32_IN_3") (pintype "bidirectional"))
    )
    (net (code "68") (name "PC15") (class "Default")
      (node (ref "R23") (pin "2") (pinfunction "2_2") (pintype "passive"))
      (node (ref "U1") (pin "4") (pinfunction "PC15-OSC32_OUT_4") (pintype "bidirectional"))
    )
    (net (code "69") (name "RESET") (class "Default")
      (node (ref "U$8") (pin "5") (pinfunction "RESET_5") (pintype "input"))
    )
    (net (code "70") (name "RST") (class "Default")
      (node (ref "C1") (pin "1") (pinfunction "1_1") (pintype "passive"))
      (node (ref "R3") (pin "1") (pinfunction "1_1") (pintype "passive"))
      (node (ref "S1") (pin "2") (pinfunction "2_2") (pintype "passive"))
      (node (ref "U1") (pin "7") (pinfunction "NRST_7") (pintype "input"))
    )
    (net (code "71") (name "RX1") (class "Default")
      (node (ref "U$12") (pin "3") (pinfunction "P$3_3") (pintype "bidirectional"))
      (node (ref "U1") (pin "31") (pinfunction "PA10_31") (pintype "bidirectional"))
    )
    (net (code "72") (name "RX2") (class "Default")
      (node (ref "JMP6") (pin "3") (pinfunction "3_3") (pintype "passive"))
      (node (ref "JMP7") (pin "1") (pinfunction "1_1") (pintype "passive"))
      (node (ref "U$11") (pin "3") (pinfunction "P$3_3") (pintype "bidirectional"))
      (node (ref "U1") (pin "13") (pinfunction "PA3_13") (pintype "bidirectional"))
    )
    (net (code "73") (name "SCL1") (class "Default")
      (node (ref "JMP1") (pin "1") (pinfunction "1_1") (pintype "passive"))
      (node (ref "U1") (pin "42") (pinfunction "PB6_42") (pintype "bidirectional"))
    )
    (net (code "74") (name "SCL2{slash}TX3") (class "Default")
      (node (ref "JMP1") (pin "3") (pinfunction "3_3") (pintype "passive"))
      (node (ref "U$7") (pin "3") (pinfunction "P$3_3") (pintype "bidirectional"))
      (node (ref "U1") (pin "21") (pinfunction "PB10_21") (pintype "bidirectional"))
    )
    (net (code "75") (name "SDA1") (class "Default")
      (node (ref "JMP2") (pin "1") (pinfunction "1_1") (pintype "passive"))
      (node (ref "U1") (pin "43") (pinfunction "PB7_43") (pintype "bidirectional"))
    )
    (net (code "76") (name "SDA2{slash}RX3") (class "Default")
      (node (ref "JMP2") (pin "3") (pinfunction "3_3") (pintype "passive"))
      (node (ref "U$7") (pin "4") (pinfunction "P$4_4") (pintype "bidirectional"))
      (node (ref "U1") (pin "22") (pinfunction "PB11_22") (pintype "bidirectional"))
    )
    (net (code "77") (name "TX1") (class "Default")
      (node (ref "U$12") (pin "4") (pinfunction "P$4_4") (pintype "bidirectional"))
      (node (ref "U1") (pin "30") (pinfunction "PA9_30") (pintype "bidirectional"))
    )
    (net (code "78") (name "TX2") (class "Default")
      (node (ref "JMP6") (pin "1") (pinfunction "1_1") (pintype "passive"))
      (node (ref "JMP7") (pin "3") (pinfunction "3_3") (pintype "passive"))
      (node (ref "U$11") (pin "4") (pinfunction "P$4_4") (pintype "bidirectional"))
      (node (ref "U1") (pin "12") (pinfunction "PA2_12") (pintype "bidirectional"))
    )
    (net (code "79") (name "UL2") (class "Default")
      (node (ref "U1") (pin "14") (pinfunction "PA4_14") (pintype "bidirectional"))
      (node (ref "U3") (pin "2") (pinfunction "ZB_2") (pintype "bidirectional"))
    )
    (net (code "80") (name "UL3") (class "Default")
      (node (ref "U1") (pin "15") (pinfunction "PA5_15") (pintype "bidirectional"))
      (node (ref "U3") (pin "3") (pinfunction "SB_3") (pintype "bidirectional"))
    )
    (net (code "81") (name "VBAT") (class "Default")
      (node (ref "U1") (pin "1") (pinfunction "VBAT_1") (pintype "bidirectional"))
    )
    (net (code "82") (name "VCC") (class "Default")
      (node (ref "C12") (pin "+") (pinfunction "+_+") (pintype "passive"))
      (node (ref "C3") (pin "1") (pinfunction "1_1") (pintype "passive"))
      (node (ref "C4") (pin "1") (pinfunction "1_1") (pintype "passive"))
      (node (ref "C6") (pin "1") (pinfunction "1_1") (pintype "passive"))
      (node (ref "C7") (pin "+") (pinfunction "+_+") (pintype "passive"))
      (node (ref "JMP10") (pin "3") (pinfunction "3_3") (pintype "passive"))
      (node (ref "JMP5") (pin "3") (pinfunction "3_3") (pintype "passive"))
      (node (ref "JMP8") (pin "3") (pinfunction "3_3") (pintype "passive"))
      (node (ref "JMP9") (pin "3") (pinfunction "3_3") (pintype "passive"))
      (node (ref "R6") (pin "2") (pinfunction "2_2") (pintype "passive"))
      (node (ref "U4") (pin "3") (pinfunction "IN_3") (pintype "input"))
      (node (ref "U6") (pin "2") (pinfunction "OUT_2") (pintype "output"))
      (node (ref "U6") (pin "4") (pinfunction "4_4") (pintype "passive"))
    )
    (net (code "83") (name "VIN") (class "Default")
      (node (ref "C10") (pin "+") (pinfunction "+_+") (pintype "passive"))
      (node (ref "C14") (pin "+") (pinfunction "+_+") (pintype "passive"))
      (node (ref "C16") (pin "+") (pinfunction "+_+") (pintype "passive"))
      (node (ref "C18") (pin "+") (pinfunction "+_+") (pintype "passive"))
      (node (ref "C29") (pin "+") (pinfunction "+_+") (pintype "passive"))
      (node (ref "C9") (pin "1") (pinfunction "1_1") (pintype "passive"))
      (node (ref "D2") (pin "C") (pinfunction "C_C") (pintype "passive"))
      (node (ref "D4") (pin "C") (pinfunction "C_C") (pintype "passive"))
      (node (ref "D5") (pin "C") (pinfunction "C_C") (pintype "passive"))
      (node (ref "D6") (pin "C") (pinfunction "C_C") (pintype "passive"))
      (node (ref "D7") (pin "C") (pinfunction "C_C") (pintype "passive"))
      (node (ref "Q1") (pin "2") (pinfunction "S_2") (pintype "passive"))
      (node (ref "Q3") (pin "2") (pinfunction "S_2") (pintype "passive"))
      (node (ref "Q4") (pin "2") (pinfunction "S_2") (pintype "passive"))
      (node (ref "Q5") (pin "2") (pinfunction "S_2") (pintype "passive"))
      (node (ref "Q6") (pin "S") (pinfunction "S_S") (pintype "bidirectional"))
      (node (ref "R15") (pin "2") (pinfunction "2_2") (pintype "passive"))
      (node (ref "R17") (pin "2") (pinfunction "2_2") (pintype "passive"))
      (node (ref "R19") (pin "2") (pinfunction "2_2") (pintype "passive"))
      (node (ref "R40") (pin "2") (pinfunction "2_2") (pintype "passive"))
      (node (ref "R41") (pin "2") (pinfunction "2_2") (pintype "passive"))
      (node (ref "U$20") (pin "P$1") (pinfunction "1_P$1") (pintype "passive"))
      (node (ref "U$22") (pin "P$1") (pinfunction "1_P$1") (pintype "passive"))
      (node (ref "U3") (pin "9") (pinfunction "COM_9") (pintype "bidirectional"))
      (node (ref "U6") (pin "3") (pinfunction "IN_3") (pintype "input"))
    )
    (net (code "84") (name "unconnected-(J1-Pad5)") (class "Default")
      (node (ref "J1") (pin "5") (pinfunction "5_5") (pintype "passive"))
    )
    (net (code "85") (name "unconnected-(J1-Pad6)") (class "Default")
      (node (ref "J1") (pin "6") (pinfunction "6_6") (pintype "passive"))
    )
    (net (code "86") (name "unconnected-(J2-Pad5)") (class "Default")
      (node (ref "J2") (pin "5") (pinfunction "5_5") (pintype "passive"))
    )
    (net (code "87") (name "unconnected-(J2-Pad6)") (class "Default")
      (node (ref "J2") (pin "6") (pinfunction "6_6") (pintype "passive"))
    )
    (net (code "88") (name "unconnected-(J2-Pad7)") (class "Default")
      (node (ref "J2") (pin "7") (pinfunction "7_7") (pintype "passive"))
    )
    (net (code "89") (name "unconnected-(J2-Pad8)") (class "Default")
      (node (ref "J2") (pin "8") (pinfunction "8_8") (pintype "passive"))
    )
    (net (code "90") (name "unconnected-(U$8-AD0{slash}DIO0-Pad20)") (class "Default")
      (node (ref "U$8") (pin "20") (pinfunction "AD0/DIO0_20") (pintype "bidirectional"))
    )
    (net (code "91") (name "unconnected-(U$8-AD1{slash}DIO1-Pad19)") (class "Default")
      (node (ref "U$8") (pin "19") (pinfunction "AD1/DIO1_19") (pintype "bidirectional"))
    )
    (net (code "92") (name "unconnected-(U$8-AD2{slash}DIO2-Pad18)") (class "Default")
      (node (ref "U$8") (pin "18") (pinfunction "AD2/DIO2_18") (pintype "bidirectional"))
    )
    (net (code "93") (name "unconnected-(U$8-AD3{slash}DIO3-Pad17)") (class "Default")
      (node (ref "U$8") (pin "17") (pinfunction "AD3/DIO3_17") (pintype "bidirectional"))
    )
    (net (code "94") (name "unconnected-(U$8-AD4{slash}DIO4-Pad11)") (class "Default")
      (node (ref "U$8") (pin "11") (pinfunction "AD4/DIO4_11") (pintype "bidirectional"))
    )
    (net (code "95") (name "unconnected-(U$8-ASC{slash}AD5{slash}DIO5-Pad15)") (class "Default")
      (node (ref "U$8") (pin "15") (pinfunction "ASC/AD5/DIO5_15") (pintype "bidirectional"))
    )
    (net (code "96") (name "unconnected-(U$8-CTS{slash}DIO7-Pad12)") (class "Default")
      (node (ref "U$8") (pin "12") (pinfunction "CTS/DIO7_12") (pintype "bidirectional"))
    )
    (net (code "97") (name "unconnected-(U$8-DO8-Pad4)") (class "Default")
      (node (ref "U$8") (pin "4") (pinfunction "DO8_4") (pintype "output"))
    )
    (net (code "98") (name "unconnected-(U$8-DTR{slash}DI8-Pad9)") (class "Default")
      (node (ref "U$8") (pin "9") (pinfunction "DTR/DI8_9") (pintype "input"))
    )
    (net (code "99") (name "unconnected-(U$8-ON{slash}SLEEP-Pad13)") (class "Default")
      (node (ref "U$8") (pin "13") (pinfunction "ON/SLEEP_13") (pintype "output"))
    )
    (net (code "100") (name "unconnected-(U$8-PWM0{slash}RSSI-Pad6)") (class "Default")
      (node (ref "U$8") (pin "6") (pinfunction "PWM0/RSSI_6") (pintype "output"))
    )
    (net (code "101") (name "unconnected-(U$8-PWM1-Pad7)") (class "Default")
      (node (ref "U$8") (pin "7") (pinfunction "PWM1_7") (pintype "output"))
    )
    (net (code "102") (name "unconnected-(U$8-RESERVED-Pad8)") (class "Default")
      (node (ref "U$8") (pin "8") (pinfunction "RESERVED_8") (pintype "no_connect"))
    )
    (net (code "103") (name "unconnected-(U$8-RTS{slash}AD6{slash}DIO6-Pad16)") (class "Default")
      (node (ref "U$8") (pin "16") (pinfunction "RTS/AD6/DIO6_16") (pintype "bidirectional"))
    )
    (net (code "104") (name "unconnected-(U$8-VREF-Pad14)") (class "Default")
      (node (ref "U$8") (pin "14") (pinfunction "VREF_14") (pintype "input"))
    )
  )
)
